# sensor_node_v2.net
KiCad netlist of a schematic drawn in EAGLE
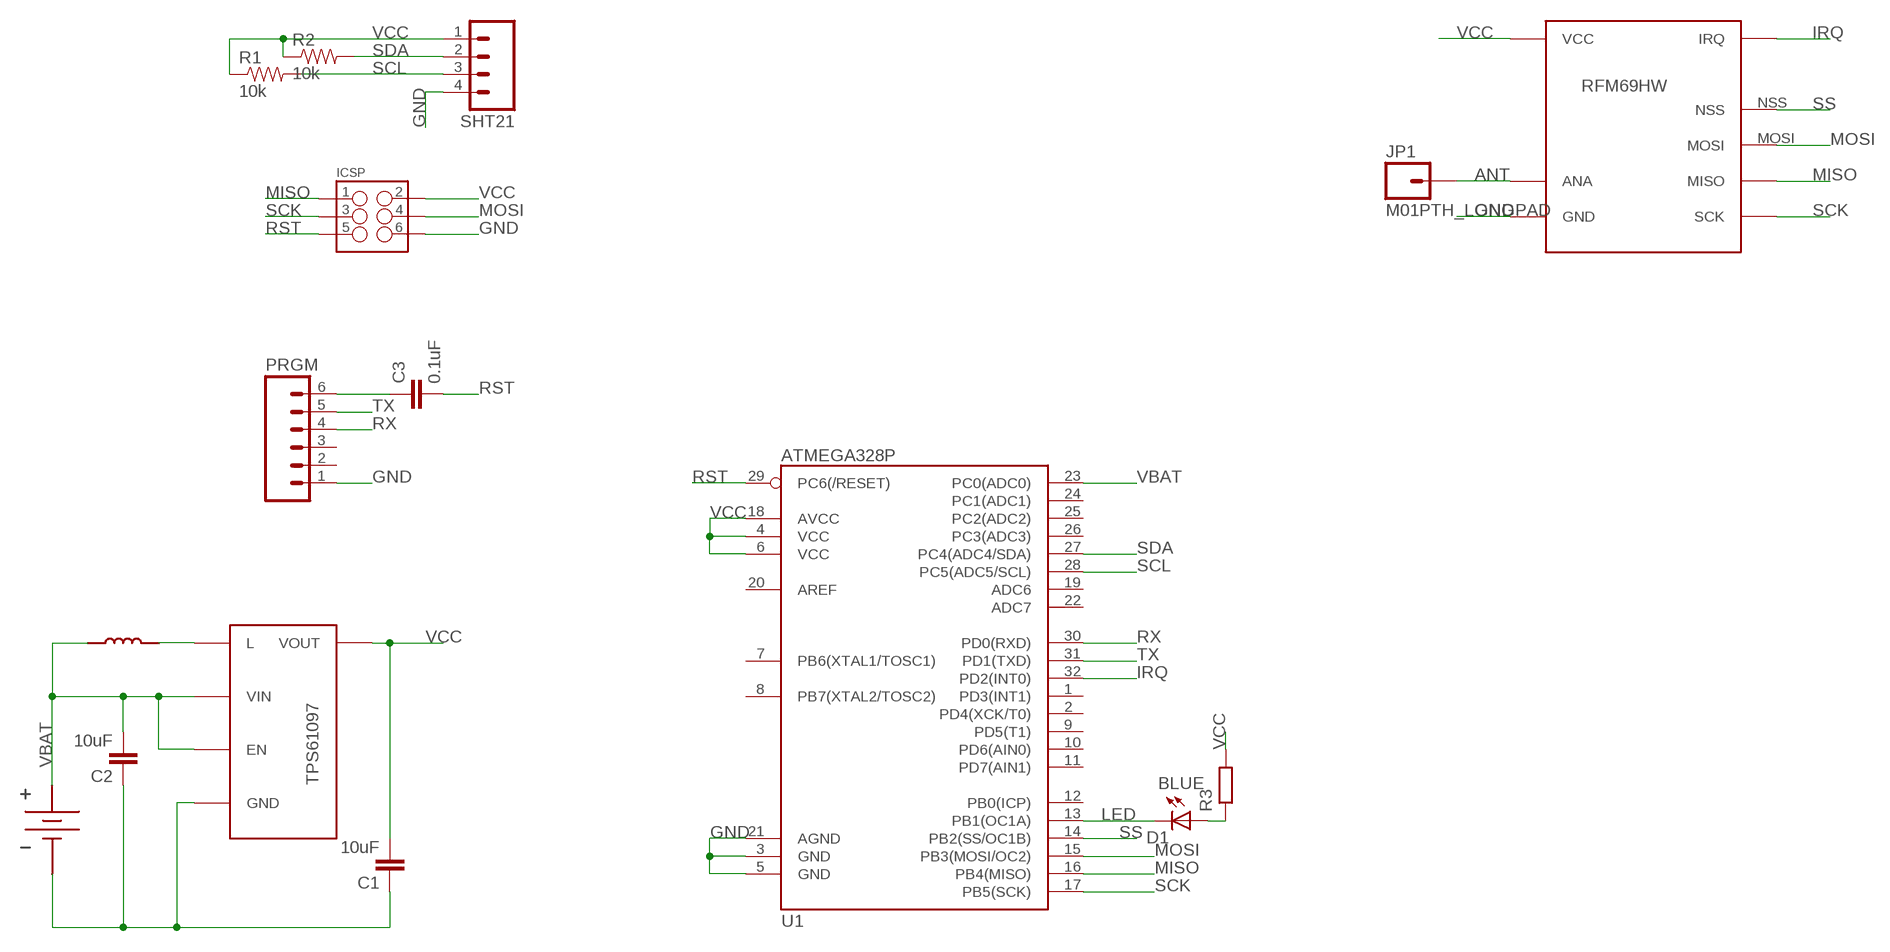
[diagram p0: schematic, sheet 1]

(export (version "E")
  (design (tool "Eeschema 10.0.6"))
  (components
    (comp (ref "C1")
      (value "10uF")
      (footprint "eagle-import:0603-CAP")
      (libsource (lib "eagle-import") (part "10UF-6.3V-20%(0603)"))
    )
    (comp (ref "C2")
      (value "10uF")
      (footprint "eagle-import:0603-CAP")
      (libsource (lib "eagle-import") (part "10UF-6.3V-20%(0603)"))
    )
    (comp (ref "C3")
      (value "0.1uF")
      (footprint "eagle-import:0603-CAP")
      (libsource (lib "eagle-import") (part "0.22UF50V-20%,+80%(0603)"))
    )
    (comp (ref "D1")
      (value "BLUE")
      (footprint "eagle-import:LED-0603")
      (libsource (lib "eagle-import") (part "LED-BLUE0603"))
    )
    (comp (ref "ICSP")
      (value "M03X2FEMALE_SMD")
      (footprint "eagle-import:2X3_SMD")
      (libsource (lib "eagle-import") (part "M03X2FEMALE_SMD"))
    )
    (comp (ref "JP1")
      (value "M01PTH_LONGPAD")
      (footprint "eagle-import:1X01_LONGPAD")
      (libsource (lib "eagle-import") (part "M01PTH_LONGPAD"))
    )
    (comp (ref "PRGM")
      (value "M06LOCK_LONGPADS")
      (footprint "eagle-import:1X06_LOCK_LONGPADS")
      (libsource (lib "eagle-import") (part "M06LOCK_LONGPADS"))
    )
    (comp (ref "R1")
      (value "10k")
      (footprint "eagle-import:0603-RES")
      (libsource (lib "eagle-import") (part "2.0KOHM1/10W5%(0603)"))
    )
    (comp (ref "R2")
      (value "10k")
      (footprint "eagle-import:0603-RES")
      (libsource (lib "eagle-import") (part "2.0KOHM1/10W5%(0603)"))
    )
    (comp (ref "R3")
      (value "RESISTOR0603-N")
      (footprint "eagle-import:R0603-N")
      (libsource (lib "eagle-import") (part "RESISTOR0603-N"))
    )
    (comp (ref "SHT21")
      (value "M04LOCK_LONGPADS")
      (footprint "eagle-import:1X04_LOCK_LONGPADS")
      (libsource (lib "eagle-import") (part "M04LOCK_LONGPADS"))
    )
    (comp (ref "U$1")
      (value "KEYSTONEAAHOLDER_2CELL")
      (footprint "eagle-import:KEYSTONEAAHOLDER_2CELL")
      (libsource (lib "eagle-import") (part "KEYSTONEAAHOLDER_2CELL"))
    )
    (comp (ref "U$2")
      (value "TPS61097-33")
      (footprint "eagle-import:SOT23-5")
      (libsource (lib "eagle-import") (part "TPS61097-33"))
    )
    (comp (ref "U$3")
      (value "COILCRAFT_DO3314")
      (footprint "eagle-import:COILCRAFT_DO3314")
      (libsource (lib "eagle-import") (part "COILCRAFT_DO3314"))
    )
    (comp (ref "U$4")
      (value "RFM69HW_MIN")
      (footprint "eagle-import:RFM69")
      (libsource (lib "eagle-import") (part "RFM69HW_MIN"))
    )
    (comp (ref "U1")
      (value "ATMEGA328P")
      (footprint "eagle-import:TQFP32-08")
      (libsource (lib "eagle-import") (part "ATMEGA328_SMT"))
    )
  )
  (nets
    (net (code "1") (name "/ANT") (class "Default")
      (node (ref "JP1") (pin "1") (pinfunction "1_1") (pintype "passive"))
      (node (ref "U$4") (pin "ANA") (pinfunction "ANA_ANA") (pintype "bidirectional"))
    )
    (net (code "2") (name "/GND") (class "Default")
      (node (ref "C1") (pin "1") (pinfunction "1_1") (pintype "passive"))
      (node (ref "C2") (pin "1") (pinfunction "1_1") (pintype "passive"))
      (node (ref "ICSP") (pin "6") (pinfunction "6_6") (pintype "bidirectional"))
      (node (ref "PRGM") (pin "1") (pinfunction "1_1") (pintype "passive"))
      (node (ref "SHT21") (pin "4") (pinfunction "4_4") (pintype "passive"))
      (node (ref "U$1") (pin "P$2") (pinfunction "GND_P$2") (pintype "bidirectional"))
      (node (ref "U$2") (pin "P$2") (pinfunction "GND_P$2") (pintype "bidirectional"))
      (node (ref "U$4") (pin "GND") (pinfunction "GND_GND") (pintype "bidirectional"))
      (node (ref "U1") (pin "21") (pinfunction "AGND_21") (pintype "bidirectional"))
      (node (ref "U1") (pin "3") (pinfunction "GND_3") (pintype "bidirectional"))
      (node (ref "U1") (pin "5") (pinfunction "GND_5") (pintype "bidirectional"))
    )
    (net (code "3") (name "/IRQ") (class "Default")
      (node (ref "U$4") (pin "DIO0") (pinfunction "IRQ_DIO0") (pintype "bidirectional"))
      (node (ref "U1") (pin "32") (pinfunction "PD2(INT0)_32") (pintype "bidirectional"))
    )
    (net (code "4") (name "/LED") (class "Default")
      (node (ref "D1") (pin "C") (pinfunction "C_C") (pintype "passive"))
      (node (ref "U1") (pin "13") (pinfunction "PB1(OC1A)_13") (pintype "bidirectional"))
    )
    (net (code "5") (name "/MISO") (class "Default")
      (node (ref "ICSP") (pin "1") (pinfunction "1_1") (pintype "bidirectional"))
      (node (ref "U$4") (pin "MISO") (pinfunction "MISO_MISO") (pintype "bidirectional"))
      (node (ref "U1") (pin "16") (pinfunction "PB4(MISO)_16") (pintype "bidirectional"))
    )
    (net (code "6") (name "/MOSI") (class "Default")
      (node (ref "ICSP") (pin "4") (pinfunction "4_4") (pintype "bidirectional"))
      (node (ref "U$4") (pin "MOSI") (pinfunction "MOSI_MOSI") (pintype "bidirectional"))
      (node (ref "U1") (pin "15") (pinfunction "PB3(MOSI/OC2)_15") (pintype "bidirectional"))
    )
    (net (code "7") (name "/RST") (class "Default")
      (node (ref "C3") (pin "2") (pinfunction "2_2") (pintype "passive"))
      (node (ref "ICSP") (pin "5") (pinfunction "5_5") (pintype "bidirectional"))
      (node (ref "U1") (pin "29") (pinfunction "PC6(/RESET)_29") (pintype "bidirectional"))
    )
    (net (code "8") (name "/RX") (class "Default")
      (node (ref "PRGM") (pin "4") (pinfunction "4_4") (pintype "passive"))
      (node (ref "U1") (pin "30") (pinfunction "PD0(RXD)_30") (pintype "bidirectional"))
    )
    (net (code "9") (name "/SCK") (class "Default")
      (node (ref "ICSP") (pin "3") (pinfunction "3_3") (pintype "bidirectional"))
      (node (ref "U$4") (pin "SCK") (pinfunction "SCK_SCK") (pintype "bidirectional"))
      (node (ref "U1") (pin "17") (pinfunction "PB5(SCK)_17") (pintype "bidirectional"))
    )
    (net (code "10") (name "/SCL") (class "Default")
      (node (ref "R1") (pin "2") (pinfunction "2_2") (pintype "passive"))
      (node (ref "SHT21") (pin "3") (pinfunction "3_3") (pintype "passive"))
      (node (ref "U1") (pin "28") (pinfunction "PC5(ADC5/SCL)_28") (pintype "bidirectional"))
    )
    (net (code "11") (name "/SDA") (class "Default")
      (node (ref "R2") (pin "2") (pinfunction "2_2") (pintype "passive"))
      (node (ref "SHT21") (pin "2") (pinfunction "2_2") (pintype "passive"))
      (node (ref "U1") (pin "27") (pinfunction "PC4(ADC4/SDA)_27") (pintype "bidirectional"))
    )
    (net (code "12") (name "/SS") (class "Default")
      (node (ref "U$4") (pin "NSS") (pinfunction "NSS_NSS") (pintype "bidirectional"))
      (node (ref "U1") (pin "14") (pinfunction "PB2(SS/OC1B)_14") (pintype "bidirectional"))
    )
    (net (code "13") (name "/TX") (class "Default")
      (node (ref "PRGM") (pin "5") (pinfunction "5_5") (pintype "passive"))
      (node (ref "U1") (pin "31") (pinfunction "PD1(TXD)_31") (pintype "bidirectional"))
    )
    (net (code "14") (name "/VBAT") (class "Default")
      (node (ref "C2") (pin "2") (pinfunction "2_2") (pintype "passive"))
      (node (ref "U$1") (pin "P$1") (pinfunction "VBAT_P$1") (pintype "bidirectional"))
      (node (ref "U$2") (pin "P$1") (pinfunction "VIN_P$1") (pintype "bidirectional"))
      (node (ref "U$2") (pin "P$3") (pinfunction "EN_P$3") (pintype "bidirectional"))
      (node (ref "U$3") (pin "P$2") (pinfunction "P$2_P$2") (pintype "bidirectional"))
      (node (ref "U1") (pin "23") (pinfunction "PC0(ADC0)_23") (pintype "bidirectional"))
    )
    (net (code "15") (name "/VCC") (class "Default")
      (node (ref "C1") (pin "2") (pinfunction "2_2") (pintype "passive"))
      (node (ref "ICSP") (pin "2") (pinfunction "2_2") (pintype "bidirectional"))
      (node (ref "R1") (pin "1") (pinfunction "1_1") (pintype "passive"))
      (node (ref "R2") (pin "1") (pinfunction "1_1") (pintype "passive"))
      (node (ref "R3") (pin "2") (pinfunction "P$2_2") (pintype "passive"))
      (node (ref "SHT21") (pin "1") (pinfunction "1_1") (pintype "passive"))
      (node (ref "U$2") (pin "P$4") (pinfunction "VOUT_P$4") (pintype "bidirectional"))
      (node (ref "U$4") (pin "VCC") (pinfunction "VCC_VCC") (pintype "bidirectional"))
      (node (ref "U1") (pin "18") (pinfunction "AVCC_18") (pintype "bidirectional"))
      (node (ref "U1") (pin "4") (pinfunction "VCC_4") (pintype "bidirectional"))
      (node (ref "U1") (pin "6") (pinfunction "VCC_6") (pintype "bidirectional"))
    )
    (net (code "16") (name "Net-(C3-Pad1)") (class "Default")
      (node (ref "C3") (pin "1") (pinfunction "1_1") (pintype "passive"))
      (node (ref "PRGM") (pin "6") (pinfunction "6_6") (pintype "passive"))
    )
    (net (code "17") (name "Net-(R3-P$1)") (class "Default")
      (node (ref "D1") (pin "A") (pinfunction "A_A") (pintype "passive"))
      (node (ref "R3") (pin "1") (pinfunction "P$1_1") (pintype "passive"))
    )
    (net (code "18") (name "Net-(U$2-L)") (class "Default")
      (node (ref "U$2") (pin "P$5") (pinfunction "L_P$5") (pintype "bidirectional"))
      (node (ref "U$3") (pin "P$1") (pinfunction "P$1_P$1") (pintype "bidirectional"))
    )
    (net (code "19") (name "unconnected-(PRGM-Pad2)") (class "Default")
      (node (ref "PRGM") (pin "2") (pinfunction "2_2") (pintype "passive"))
    )
    (net (code "20") (name "unconnected-(PRGM-Pad3)") (class "Default")
      (node (ref "PRGM") (pin "3") (pinfunction "3_3") (pintype "passive"))
    )
    (net (code "21") (name "unconnected-(U1-ADC6-Pad19)") (class "Default")
      (node (ref "U1") (pin "19") (pinfunction "ADC6_19") (pintype "bidirectional"))
    )
    (net (code "22") (name "unconnected-(U1-ADC7-Pad22)") (class "Default")
      (node (ref "U1") (pin "22") (pinfunction "ADC7_22") (pintype "bidirectional"))
    )
    (net (code "23") (name "unconnected-(U1-AREF-Pad20)") (class "Default")
      (node (ref "U1") (pin "20") (pinfunction "AREF_20") (pintype "bidirectional"))
    )
    (net (code "24") (name "unconnected-(U1-PB0(ICP)-Pad12)") (class "Default")
      (node (ref "U1") (pin "12") (pinfunction "PB0(ICP)_12") (pintype "bidirectional"))
    )
    (net (code "25") (name "unconnected-(U1-PB6(XTAL1{slash}TOSC1)-Pad7)") (class "Default")
      (node (ref "U1") (pin "7") (pinfunction "PB6(XTAL1/TOSC1)_7") (pintype "bidirectional"))
    )
    (net (code "26") (name "unconnected-(U1-PB7(XTAL2{slash}TOSC2)-Pad8)") (class "Default")
      (node (ref "U1") (pin "8") (pinfunction "PB7(XTAL2/TOSC2)_8") (pintype "bidirectional"))
    )
    (net (code "27") (name "unconnected-(U1-PC1(ADC1)-Pad24)") (class "Default")
      (node (ref "U1") (pin "24") (pinfunction "PC1(ADC1)_24") (pintype "bidirectional"))
    )
    (net (code "28") (name "unconnected-(U1-PC2(ADC2)-Pad25)") (class "Default")
      (node (ref "U1") (pin "25") (pinfunction "PC2(ADC2)_25") (pintype "bidirectional"))
    )
    (net (code "29") (name "unconnected-(U1-PC3(ADC3)-Pad26)") (class "Default")
      (node (ref "U1") (pin "26") (pinfunction "PC3(ADC3)_26") (pintype "bidirectional"))
    )
    (net (code "30") (name "unconnected-(U1-PD3(INT1)-Pad1)") (class "Default")
      (node (ref "U1") (pin "1") (pinfunction "PD3(INT1)_1") (pintype "bidirectional"))
    )
    (net (code "31") (name "unconnected-(U1-PD4(XCK{slash}T0)-Pad2)") (class "Default")
      (node (ref "U1") (pin "2") (pinfunction "PD4(XCK/T0)_2") (pintype "bidirectional"))
    )
    (net (code "32") (name "unconnected-(U1-PD5(T1)-Pad9)") (class "Default")
      (node (ref "U1") (pin "9") (pinfunction "PD5(T1)_9") (pintype "bidirectional"))
    )
    (net (code "33") (name "unconnected-(U1-PD6(AIN0)-Pad10)") (class "Default")
      (node (ref "U1") (pin "10") (pinfunction "PD6(AIN0)_10") (pintype "bidirectional"))
    )
    (net (code "34") (name "unconnected-(U1-PD7(AIN1)-Pad11)") (class "Default")
      (node (ref "U1") (pin "11") (pinfunction "PD7(AIN1)_11") (pintype "bidirectional"))
    )
  )
)
